# microcontrolador.net
KiCad netlist of a schematic drawn in Altium Designer
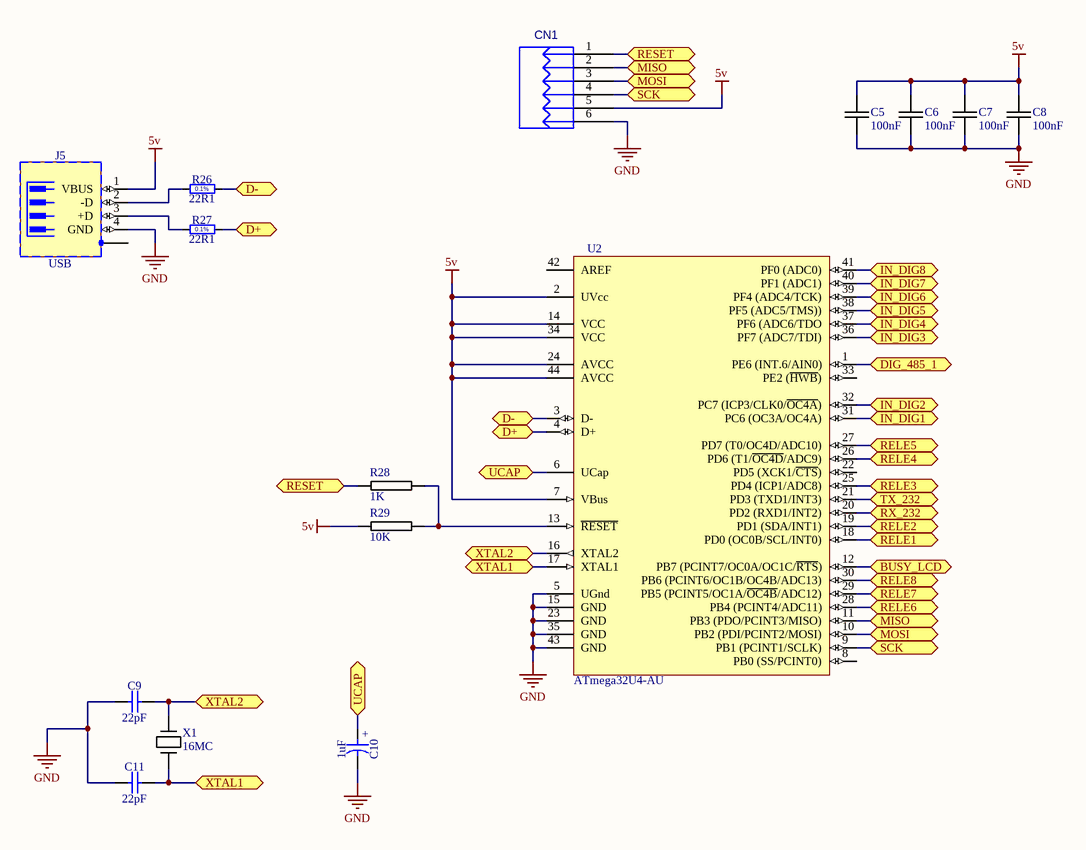
[diagram p0: microcontrolador.SchDoc]

(export (version "E")
  (design (tool "Eeschema 10.0.6"))
  (components
    (comp (ref "C5")
      (value "100nF")
      (footprint "0805C-TBD")
      (description "CAPACITOR 0805 CERAMIC")
      (libsource (lib "vh_altium_library") (part "0805C-100nF-25V-X7R-MUR"))
    )
    (comp (ref "C6")
      (value "100nF")
      (footprint "0805C-TBD")
      (description "CAPACITOR 0805 CERAMIC")
      (libsource (lib "vh_altium_library") (part "0805C-100nF-25V-X7R-MUR"))
    )
    (comp (ref "C7")
      (value "100nF")
      (footprint "0805C-TBD")
      (description "CAPACITOR 0805 CERAMIC")
      (libsource (lib "vh_altium_library") (part "0805C-100nF-25V-X7R-MUR"))
    )
    (comp (ref "C8")
      (value "100nF")
      (footprint "0805C-TBD")
      (description "CAPACITOR 0805 CERAMIC")
      (libsource (lib "vh_altium_library") (part "0805C-100nF-25V-X7R-MUR"))
    )
    (comp (ref "C9")
      (value "22pF")
      (footprint "CAPC2012X135N")
      (description "Non-polarised capacitor")
      (fields
        (field (name "PART NUMBER") "CC0805_22PF_50V_5%_NP0")
        (field (name "VOLTAGE") "50V")
        (field (name "AUTHOR") "CERN DEM JLC")
      )
      (libsource (lib "Capacitors") (part "Capacitor - non polarized"))
    )
    (comp (ref "C10")
      (value "1uF")
      (footprint "CAPPRB254-450X710")
      (description "Polarised capacitor")
      (fields
        (field (name "PART NUMBER") "CTEB_1UF_35V_10%_254-450X710")
        (field (name "VOLTAGE") "35V")
        (field (name "AUTHOR") "CERN DEM JLC")
      )
      (libsource (lib "Capacitors") (part "Capacitor - polarized"))
    )
    (comp (ref "C11")
      (value "22pF")
      (footprint "CAPC2012X135N")
      (description "Non-polarised capacitor")
      (fields
        (field (name "PART NUMBER") "CC0805_22PF_50V_5%_NP0")
        (field (name "VOLTAGE") "50V")
        (field (name "AUTHOR") "CERN DEM JLC")
      )
      (libsource (lib "Capacitors") (part "Capacitor - non polarized"))
    )
    (comp (ref "CN1")
      (value "CONECTOR 2,5 - 6VIAS AMP 880222-6")
      (footprint "CONECTOR 2.5 - 6 VIAS AMP 880222-6")
      (libsource (lib "GNATUS_COMPONENTES_BASE") (part "CONECTOR 2,5 - 6VIAS AMP 880222-6"))
    )
    (comp (ref "J5")
      (value "USB")
      (footprint "TYCO_292304-1")
      (description "4 Pin + 1 Shield USB Receptacle")
      (fields
        (field (name "PART NUMBER") "TYCO_292304-1")
        (field (name "MANUFACTURER") "TYCO ELECTRONICS")
        (field (name "AUTHOR") "CERN DEM JLC")
      )
      (libsource (lib "Connectors") (part "Connector USB 4 Pin + 1Shield"))
    )
    (comp (ref "R26")
      (value "22R1")
      (footprint "RESC2012X60N")
      (description "Resistor - 0.1%")
      (fields
        (field (name "PART NUMBER") "R0805_22R1_0.1%_0.1W_10PPM")
        (field (name "POWER") "0.1W")
        (field (name "AUTHOR") "CERN DEM JLC")
      )
      (libsource (lib "Resistors") (part "Resistor - 0.1%"))
    )
    (comp (ref "R27")
      (value "22R1")
      (footprint "RESC2012X60N")
      (description "Resistor - 0.1%")
      (fields
        (field (name "PART NUMBER") "R0805_22R1_0.1%_0.1W_10PPM")
        (field (name "POWER") "0.1W")
        (field (name "AUTHOR") "CERN DEM JLC")
      )
      (libsource (lib "Resistors") (part "Resistor - 0.1%"))
    )
    (comp (ref "R28")
      (value "1K")
      (footprint "0805R-1K")
      (description "RESISTOR 0805 1/4 WATT THIN FILM")
      (libsource (lib "vh_altium_library") (part "0805R-1K"))
    )
    (comp (ref "R29")
      (value "10K")
      (footprint "0805R-10K")
      (description "RESISTOR 0805 1/4 WATT THIN FILM")
      (libsource (lib "vh_altium_library") (part "0805R-10K"))
    )
    (comp (ref "U2")
      (value "ATmega32U4-AU")
      (footprint "44ML_N")
      (libsource (lib "Atmel Microcontroller megaAVR") (part "ATmega32U4-AU"))
    )
    (comp (ref "X1")
      (value "16MC")
      (footprint "XTAL-RU49/4")
      (description "16MHZ CRSYTAL HC49US")
      (libsource (lib "vh_altium_library") (part "16MC-HC49US"))
    )
  )
  (nets
    (net (code "1") (name "/BUSY_LCD") (class "Default")
      (node (ref "U2") (pin "12") (pinfunction "PB7_(PCINT7/OC0A/OC1C/~{RTS})_12") (pintype "bidirectional"))
    )
    (net (code "2") (name "/D+") (class "Default")
      (node (ref "R27") (pin "2") (pinfunction "2_2") (pintype "passive"))
      (node (ref "U2") (pin "4") (pinfunction "D+_4") (pintype "bidirectional"))
    )
    (net (code "3") (name "/D-") (class "Default")
      (node (ref "R26") (pin "2") (pinfunction "2_2") (pintype "passive"))
      (node (ref "U2") (pin "3") (pinfunction "D-_3") (pintype "bidirectional"))
    )
    (net (code "4") (name "/DIG_485_1") (class "Default")
      (node (ref "U2") (pin "1") (pinfunction "PE6_(INT.6/AIN0)_1") (pintype "bidirectional"))
    )
    (net (code "5") (name "/IN_DIG1") (class "Default")
      (node (ref "U2") (pin "31") (pinfunction "PC6_(OC3A/OC4A)_31") (pintype "bidirectional"))
    )
    (net (code "6") (name "/IN_DIG2") (class "Default")
      (node (ref "U2") (pin "32") (pinfunction "PC7_(ICP3/CLK0/~{OC4A})_32") (pintype "bidirectional"))
    )
    (net (code "7") (name "/IN_DIG3") (class "Default")
      (node (ref "U2") (pin "36") (pinfunction "PF7_(ADC7/TDI)_36") (pintype "bidirectional"))
    )
    (net (code "8") (name "/IN_DIG4") (class "Default")
      (node (ref "U2") (pin "37") (pinfunction "PF6_(ADC6/TDO_37") (pintype "bidirectional"))
    )
    (net (code "9") (name "/IN_DIG5") (class "Default")
      (node (ref "U2") (pin "38") (pinfunction "PF5_(ADC5/TMS))_38") (pintype "bidirectional"))
    )
    (net (code "10") (name "/IN_DIG6") (class "Default")
      (node (ref "U2") (pin "39") (pinfunction "PF4_(ADC4/TCK)_39") (pintype "bidirectional"))
    )
    (net (code "11") (name "/IN_DIG7") (class "Default")
      (node (ref "U2") (pin "40") (pinfunction "PF1_(ADC1)_40") (pintype "bidirectional"))
    )
    (net (code "12") (name "/IN_DIG8") (class "Default")
      (node (ref "U2") (pin "41") (pinfunction "PF0_(ADC0)_41") (pintype "bidirectional"))
    )
    (net (code "13") (name "/MISO") (class "Default")
      (node (ref "CN1") (pin "2") (pinfunction "2_2") (pintype "passive"))
      (node (ref "U2") (pin "11") (pinfunction "PB3_(PDO/PCINT3/MISO)_11") (pintype "bidirectional"))
    )
    (net (code "14") (name "/MOSI") (class "Default")
      (node (ref "CN1") (pin "3") (pinfunction "3_3") (pintype "passive"))
      (node (ref "U2") (pin "10") (pinfunction "PB2_(PDI/PCINT2/MOSI)_10") (pintype "bidirectional"))
    )
    (net (code "15") (name "/RELE1") (class "Default")
      (node (ref "U2") (pin "18") (pinfunction "PD0_(OC0B/SCL/INT0)_18") (pintype "bidirectional"))
    )
    (net (code "16") (name "/RELE2") (class "Default")
      (node (ref "U2") (pin "19") (pinfunction "PD1_(SDA/INT1)_19") (pintype "bidirectional"))
    )
    (net (code "17") (name "/RELE3") (class "Default")
      (node (ref "U2") (pin "25") (pinfunction "PD4_(ICP1/ADC8)_25") (pintype "bidirectional"))
    )
    (net (code "18") (name "/RELE4") (class "Default")
      (node (ref "U2") (pin "26") (pinfunction "PD6_(T1/~{OC4D}/ADC9)_26") (pintype "bidirectional"))
    )
    (net (code "19") (name "/RELE5") (class "Default")
      (node (ref "U2") (pin "27") (pinfunction "PD7_(T0/OC4D/ADC10)_27") (pintype "bidirectional"))
    )
    (net (code "20") (name "/RELE6") (class "Default")
      (node (ref "U2") (pin "28") (pinfunction "PB4_(PCINT4/ADC11)_28") (pintype "bidirectional"))
    )
    (net (code "21") (name "/RELE7") (class "Default")
      (node (ref "U2") (pin "29") (pinfunction "PB5_(PCINT5/OC1A/~{OC4B}/ADC12)_29") (pintype "bidirectional"))
    )
    (net (code "22") (name "/RELE8") (class "Default")
      (node (ref "U2") (pin "30") (pinfunction "PB6_(PCINT6/OC1B/OC4B/ADC13)_30") (pintype "bidirectional"))
    )
    (net (code "23") (name "/RESET") (class "Default")
      (node (ref "CN1") (pin "1") (pinfunction "1_1") (pintype "passive"))
      (node (ref "R28") (pin "1") (pintype "passive"))
    )
    (net (code "24") (name "/RX_232") (class "Default")
      (node (ref "U2") (pin "20") (pinfunction "PD2_(RXD1/INT2)_20") (pintype "bidirectional"))
    )
    (net (code "25") (name "/SCK") (class "Default")
      (node (ref "CN1") (pin "4") (pinfunction "4_4") (pintype "passive"))
      (node (ref "U2") (pin "9") (pinfunction "PB1_(PCINT1/SCLK)_9") (pintype "bidirectional"))
    )
    (net (code "26") (name "/TX_232") (class "Default")
      (node (ref "U2") (pin "21") (pinfunction "PD3_(TXD1/INT3)_21") (pintype "bidirectional"))
    )
    (net (code "27") (name "/UCAP") (class "Default")
      (node (ref "C10") (pin "1") (pinfunction "1_1") (pintype "passive"))
      (node (ref "U2") (pin "6") (pinfunction "UCap_6") (pintype "passive"))
    )
    (net (code "28") (name "/XTAL1") (class "Default")
      (node (ref "C11") (pin "2") (pinfunction "2_2") (pintype "passive"))
      (node (ref "U2") (pin "17") (pinfunction "XTAL1_17") (pintype "input"))
      (node (ref "X1") (pin "2") (pintype "passive"))
    )
    (net (code "29") (name "/XTAL2") (class "Default")
      (node (ref "C9") (pin "2") (pinfunction "2_2") (pintype "passive"))
      (node (ref "U2") (pin "16") (pinfunction "XTAL2_16") (pintype "output"))
      (node (ref "X1") (pin "1") (pintype "passive"))
    )
    (net (code "30") (name "5v") (class "Default")
      (node (ref "C5") (pin "2") (pintype "passive"))
      (node (ref "C6") (pin "2") (pintype "passive"))
      (node (ref "C7") (pin "2") (pintype "passive"))
      (node (ref "C8") (pin "2") (pintype "passive"))
      (node (ref "CN1") (pin "5") (pinfunction "5_5") (pintype "passive"))
      (node (ref "J5") (pin "1") (pinfunction "VBUS_1") (pintype "bidirectional"))
      (node (ref "R29") (pin "1") (pintype "passive"))
      (node (ref "U2") (pin "14") (pinfunction "VCC_14") (pintype "power_in"))
      (node (ref "U2") (pin "2") (pinfunction "UVcc_2") (pintype "power_in"))
      (node (ref "U2") (pin "24") (pinfunction "AVCC_24") (pintype "power_in"))
      (node (ref "U2") (pin "34") (pinfunction "VCC_34") (pintype "power_in"))
      (node (ref "U2") (pin "44") (pinfunction "AVCC_44") (pintype "power_in"))
      (node (ref "U2") (pin "7") (pinfunction "VBus_7") (pintype "input"))
    )
    (net (code "31") (name "GND") (class "Default")
      (node (ref "C10") (pin "2") (pinfunction "2_2") (pintype "passive"))
      (node (ref "C11") (pin "1") (pinfunction "1_1") (pintype "passive"))
      (node (ref "C5") (pin "1") (pintype "passive"))
      (node (ref "C6") (pin "1") (pintype "passive"))
      (node (ref "C7") (pin "1") (pintype "passive"))
      (node (ref "C8") (pin "1") (pintype "passive"))
      (node (ref "C9") (pin "1") (pinfunction "1_1") (pintype "passive"))
      (node (ref "CN1") (pin "6") (pinfunction "6_6") (pintype "passive"))
      (node (ref "J5") (pin "4") (pinfunction "GND_4") (pintype "bidirectional"))
      (node (ref "U2") (pin "15") (pinfunction "GND_15") (pintype "power_in"))
      (node (ref "U2") (pin "23") (pinfunction "GND_23") (pintype "power_in"))
      (node (ref "U2") (pin "35") (pinfunction "GND_35") (pintype "power_in"))
      (node (ref "U2") (pin "43") (pinfunction "GND_43") (pintype "power_in"))
      (node (ref "U2") (pin "5") (pinfunction "UGnd_5") (pintype "power_in"))
    )
    (net (code "32") (name "Net-(J5-+D)") (class "Default")
      (node (ref "J5") (pin "3") (pinfunction "+D_3") (pintype "bidirectional"))
      (node (ref "R27") (pin "1") (pinfunction "1_1") (pintype "passive"))
    )
    (net (code "33") (name "Net-(J5--D)") (class "Default")
      (node (ref "J5") (pin "2") (pinfunction "-D_2") (pintype "bidirectional"))
      (node (ref "R26") (pin "1") (pinfunction "1_1") (pintype "passive"))
    )
    (net (code "34") (name "Net-(U2-~{RESET})") (class "Default")
      (node (ref "R28") (pin "2") (pintype "passive"))
      (node (ref "R29") (pin "2") (pintype "passive"))
      (node (ref "U2") (pin "13") (pinfunction "~{RESET}_13") (pintype "input"))
    )
    (net (code "35") (name "unconnected-(J5-SHIELD-Pad5)") (class "Default")
      (node (ref "J5") (pin "5") (pinfunction "SHIELD_5") (pintype "power_in"))
    )
    (net (code "36") (name "unconnected-(U2-AREF-Pad42)") (class "Default")
      (node (ref "U2") (pin "42") (pinfunction "AREF_42") (pintype "passive"))
    )
    (net (code "37") (name "unconnected-(U2-PB0_(SS{slash}PCINT0)-Pad8)") (class "Default")
      (node (ref "U2") (pin "8") (pinfunction "PB0_(SS/PCINT0)_8") (pintype "bidirectional"))
    )
    (net (code "38") (name "unconnected-(U2-PD5_(XCK1{slash}~{CTS})-Pad22)") (class "Default")
      (node (ref "U2") (pin "22") (pinfunction "PD5_(XCK1/~{CTS})_22") (pintype "bidirectional"))
    )
    (net (code "39") (name "unconnected-(U2-PE2_(~{HWB})-Pad33)") (class "Default")
      (node (ref "U2") (pin "33") (pinfunction "PE2_(~{HWB})_33") (pintype "bidirectional"))
    )
  )
)
